# BLE113.net
KiCad netlist of a schematic drawn in Altium Designer
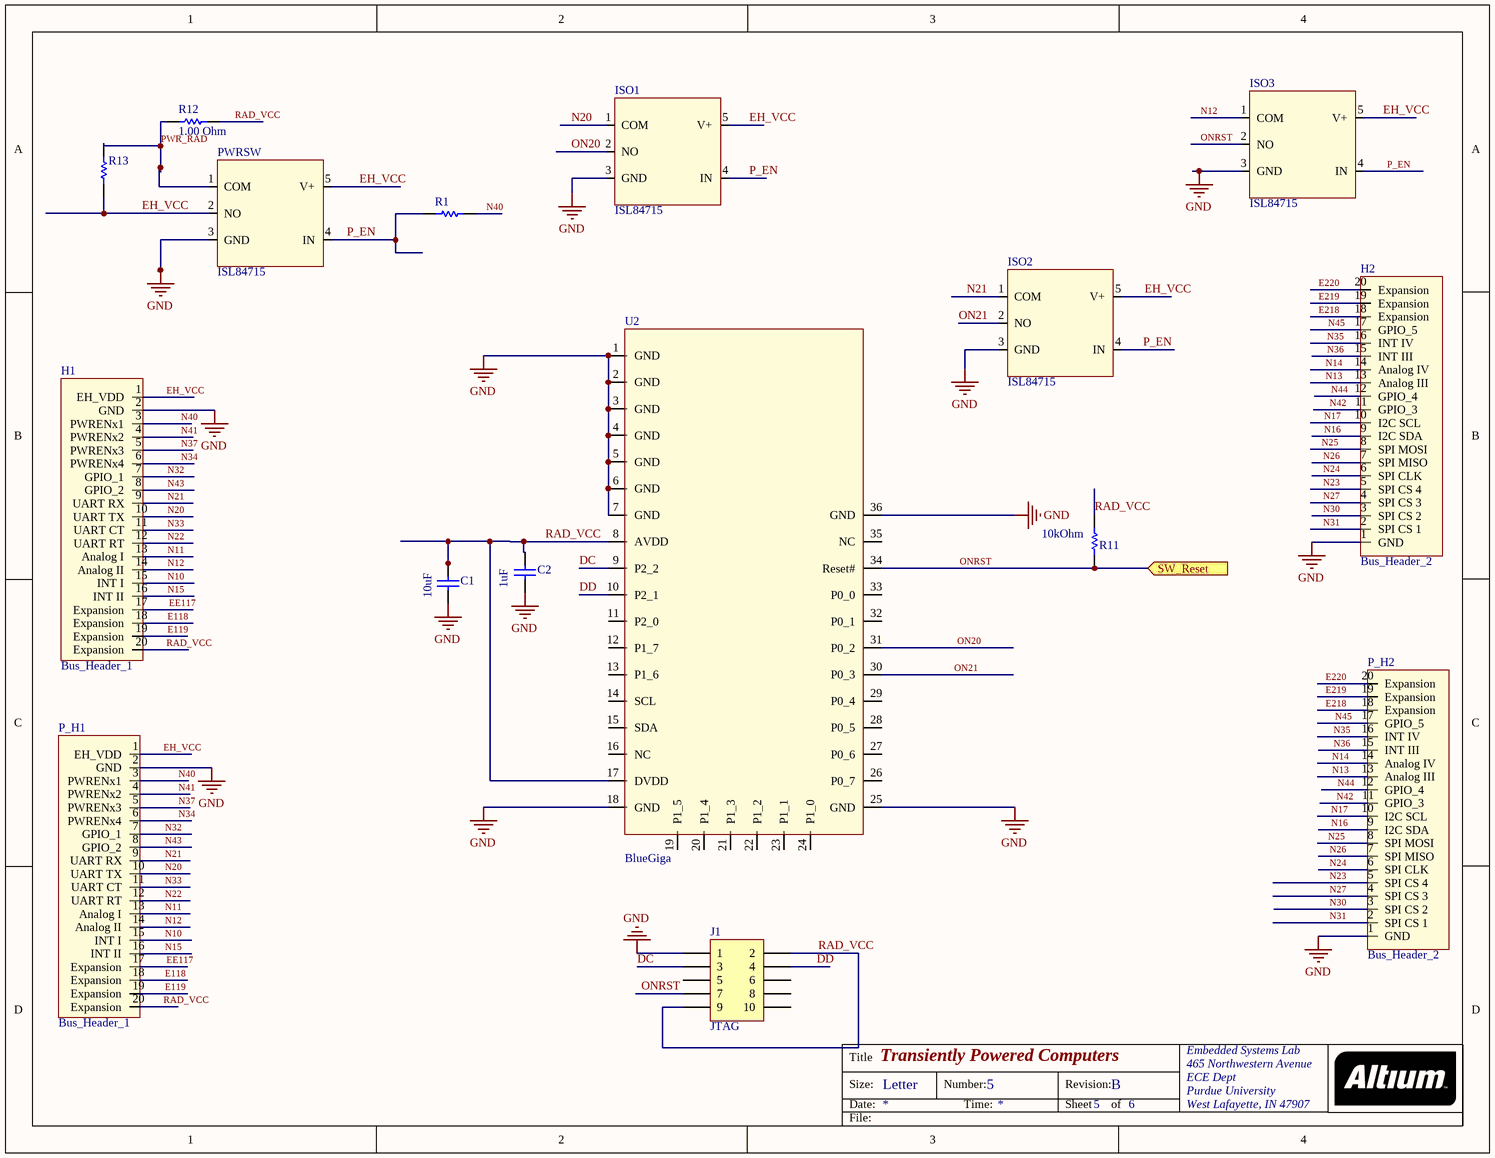
[diagram p0: BLE113.SchDoc]

(export (version "E")
  (design (tool "Eeschema 10.0.6"))
  (components
    (comp (ref "C1")
      (value "10uF")
      (footprint "CAPC0402(1005)60_N")
      (description "CAP 470nF 4V ±10% 0402 (1005 Metric) Thickness 0.6mm SMD")
      (fields (field (name "TOLERANCE") "±10%") (field (name "Comment") "CAP 470nF 4V 0402(1005)"))
      (libsource (lib "Altium Content Vault") (part "CMP-1034-02101-1"))
    )
    (comp (ref "C2")
      (value "1uF")
      (footprint "CAPC0402(1005)60_N")
      (description "CAP 470nF 4V ±10% 0402 (1005 Metric) Thickness 0.6mm SMD")
      (fields (field (name "TOLERANCE") "±10%") (field (name "Comment") "CAP 470nF 4V 0402(1005)"))
      (libsource (lib "Altium Content Vault") (part "CMP-1034-02101-1"))
    )
    (comp (ref "H1")
      (value "Bus_Header_1")
      (footprint "Male Single row 20 pin header")
      (libsource (lib "") (part "Bus_Header_1_1"))
    )
    (comp (ref "H2")
      (value "Bus_Header_2")
      (footprint "Male Single row 20 pin header")
      (libsource (lib "Basic_components_hrishi") (part "Bus_Header_2"))
    )
    (comp (ref "ISO1")
      (value "ISL84715")
      (footprint "ISL84715")
      (libsource (lib "Basic_components_hrishi") (part "ISL84715"))
    )
    (comp (ref "ISO2")
      (value "ISL84715")
      (footprint "ISL84715")
      (libsource (lib "Basic_components_hrishi") (part "ISL84715"))
    )
    (comp (ref "ISO3")
      (value "ISL84715")
      (footprint "ISL84715")
      (libsource (lib "Basic_components_hrishi") (part "ISL84715"))
    )
    (comp (ref "J1")
      (value "JTAG")
      (footprint "FTSH-105-XX-X-DV")
      (description "CC_JTAG")
      (libsource (lib "UPLINK-RX") (part "CC_JTAG"))
    )
    (comp (ref "PWRSW")
      (value "ISL84715")
      (footprint "ISL84715")
      (libsource (lib "Basic_components_hrishi") (part "ISL84715"))
    )
    (comp (ref "P_H1")
      (value "Bus_Header_1")
      (footprint "SMT 20 -pin single row female header")
      (libsource (lib "Basic_components_hrishi") (part "Bus_Header_1"))
    )
    (comp (ref "P_H2")
      (value "Bus_Header_2")
      (footprint "SMT 20 -pin single row female header")
      (libsource (lib "Basic_components_hrishi") (part "Bus_Header_2"))
    )
    (comp (ref "R1")
      (value "Jumper 0402(1005)")
      (footprint "RESC0402(1005)_N")
      (description "Jumper 0402 (1005 Metric)")
      (fields (field (name "TOLERANCE") "None"))
      (libsource (lib "Altium Content Vault") (part "CMP-1011-00001-1"))
    )
    (comp (ref "R11")
      (value "10kOhm")
      (footprint "RESC0805(2012)_M")
      (description "5R1 0.125W 5% 0805 (2012 Metric)  SMD")
      (fields (field (name "POWER") "0.125 W") (field (name "TOLERANCE") "5 %"))
      (libsource (lib "Altium Content Vault") (part "CMP-1013-00019-1"))
    )
    (comp (ref "R12")
      (value "1.00 Ohm")
      (footprint "RESC0402(1005)_N")
      (description "1R 0.063W 5% 0402 (1005 Metric)  SMD")
      (fields (field (name "POWER") "0.063 W") (field (name "TOLERANCE") "5 %"))
      (libsource (lib "Altium Content Vault") (part "CMP-1011-00002-1"))
    )
    (comp (ref "R13")
      (value "Jumper 0402(1005)")
      (footprint "RESC0402(1005)_N")
      (description "Jumper 0402 (1005 Metric)")
      (fields (field (name "TOLERANCE") "None"))
      (libsource (lib "Altium Content Vault") (part "CMP-1011-00001-1"))
    )
    (comp (ref "U2")
      (value "BlueGiga")
      (footprint "BlueGiga")
      (libsource (lib "Basic_components_hrishi") (part "BlueGiga"))
    )
  )
  (nets
    (net (code "1") (name "/DC") (class "Default")
      (node (ref "J1") (pin "3") (pinfunction "3_3") (pintype "passive"))
      (node (ref "U2") (pin "9") (pinfunction "P2_2_9") (pintype "passive"))
    )
    (net (code "2") (name "/DD") (class "Default")
      (node (ref "J1") (pin "4") (pinfunction "4_4") (pintype "passive"))
      (node (ref "U2") (pin "10") (pinfunction "P2_1_10") (pintype "passive"))
    )
    (net (code "3") (name "/E118") (class "Default")
      (node (ref "H1") (pin "18") (pinfunction "Expansion_18") (pintype "passive"))
      (node (ref "P_H1") (pin "18") (pinfunction "Expansion_18") (pintype "passive"))
    )
    (net (code "4") (name "/E119") (class "Default")
      (node (ref "H1") (pin "19") (pinfunction "Expansion_19") (pintype "passive"))
      (node (ref "P_H1") (pin "19") (pinfunction "Expansion_19") (pintype "passive"))
    )
    (net (code "5") (name "/E218") (class "Default")
      (node (ref "H2") (pin "18") (pinfunction "Expansion_18") (pintype "passive"))
      (node (ref "P_H2") (pin "18") (pinfunction "Expansion_18") (pintype "passive"))
    )
    (net (code "6") (name "/E219") (class "Default")
      (node (ref "H2") (pin "19") (pinfunction "Expansion_19") (pintype "passive"))
      (node (ref "P_H2") (pin "19") (pinfunction "Expansion_19") (pintype "passive"))
    )
    (net (code "7") (name "/E220") (class "Default")
      (node (ref "H2") (pin "20") (pinfunction "Expansion_20") (pintype "passive"))
      (node (ref "P_H2") (pin "20") (pinfunction "Expansion_20") (pintype "passive"))
    )
    (net (code "8") (name "/EE117") (class "Default")
      (node (ref "H1") (pin "17") (pinfunction "Expansion_17") (pintype "passive"))
      (node (ref "P_H1") (pin "17") (pinfunction "Expansion_17") (pintype "passive"))
    )
    (net (code "9") (name "/EH_VCC") (class "Default")
      (node (ref "H1") (pin "1") (pinfunction "EH_VDD_1") (pintype "passive"))
      (node (ref "ISO1") (pin "5") (pinfunction "V+_5") (pintype "passive"))
      (node (ref "ISO2") (pin "5") (pinfunction "V+_5") (pintype "passive"))
      (node (ref "ISO3") (pin "5") (pinfunction "V+_5") (pintype "passive"))
      (node (ref "PWRSW") (pin "2") (pinfunction "NO_2") (pintype "passive"))
      (node (ref "PWRSW") (pin "5") (pinfunction "V+_5") (pintype "passive"))
      (node (ref "P_H1") (pin "1") (pinfunction "EH_VDD_1") (pintype "passive"))
      (node (ref "R13") (pin "1") (pinfunction "1_1") (pintype "passive"))
    )
    (net (code "10") (name "/N10") (class "Default")
      (node (ref "H1") (pin "15") (pinfunction "INT_I_15") (pintype "passive"))
      (node (ref "P_H1") (pin "15") (pinfunction "INT_I_15") (pintype "passive"))
    )
    (net (code "11") (name "/N11") (class "Default")
      (node (ref "H1") (pin "13") (pinfunction "Analog_I_13") (pintype "passive"))
      (node (ref "P_H1") (pin "13") (pinfunction "Analog_I_13") (pintype "passive"))
    )
    (net (code "12") (name "/N12") (class "Default")
      (node (ref "H1") (pin "14") (pinfunction "Analog_II_14") (pintype "passive"))
      (node (ref "ISO3") (pin "1") (pinfunction "COM_1") (pintype "passive"))
      (node (ref "P_H1") (pin "14") (pinfunction "Analog_II_14") (pintype "passive"))
    )
    (net (code "13") (name "/N13") (class "Default")
      (node (ref "H2") (pin "13") (pinfunction "Analog_III_13") (pintype "passive"))
      (node (ref "P_H2") (pin "13") (pinfunction "Analog_III_13") (pintype "passive"))
    )
    (net (code "14") (name "/N14") (class "Default")
      (node (ref "H2") (pin "14") (pinfunction "Analog_IV_14") (pintype "passive"))
      (node (ref "P_H2") (pin "14") (pinfunction "Analog_IV_14") (pintype "passive"))
    )
    (net (code "15") (name "/N15") (class "Default")
      (node (ref "H1") (pin "16") (pinfunction "INT_II_16") (pintype "passive"))
      (node (ref "P_H1") (pin "16") (pinfunction "INT_II_16") (pintype "passive"))
    )
    (net (code "16") (name "/N16") (class "Default")
      (node (ref "H2") (pin "9") (pinfunction "I2C_SDA_9") (pintype "passive"))
      (node (ref "P_H2") (pin "9") (pinfunction "I2C_SDA_9") (pintype "passive"))
    )
    (net (code "17") (name "/N17") (class "Default")
      (node (ref "H2") (pin "10") (pinfunction "I2C_SCL_10") (pintype "passive"))
      (node (ref "P_H2") (pin "10") (pinfunction "I2C_SCL_10") (pintype "passive"))
    )
    (net (code "18") (name "/N20") (class "Default")
      (node (ref "H1") (pin "10") (pinfunction "UART_TX_10") (pintype "passive"))
      (node (ref "ISO1") (pin "1") (pinfunction "COM_1") (pintype "passive"))
      (node (ref "P_H1") (pin "10") (pinfunction "UART_TX_10") (pintype "passive"))
    )
    (net (code "19") (name "/N21") (class "Default")
      (node (ref "H1") (pin "9") (pinfunction "UART_RX_9") (pintype "passive"))
      (node (ref "ISO2") (pin "1") (pinfunction "COM_1") (pintype "passive"))
      (node (ref "P_H1") (pin "9") (pinfunction "UART_RX_9") (pintype "passive"))
    )
    (net (code "20") (name "/N22") (class "Default")
      (node (ref "H1") (pin "12") (pinfunction "UART_RT_12") (pintype "passive"))
      (node (ref "P_H1") (pin "12") (pinfunction "UART_RT_12") (pintype "passive"))
    )
    (net (code "21") (name "/N23") (class "Default")
      (node (ref "H2") (pin "5") (pinfunction "SPI_CS_4_5") (pintype "passive"))
      (node (ref "P_H2") (pin "5") (pinfunction "SPI_CS_4_5") (pintype "passive"))
    )
    (net (code "22") (name "/N24") (class "Default")
      (node (ref "H2") (pin "6") (pinfunction "SPI_CLK_6") (pintype "passive"))
      (node (ref "P_H2") (pin "6") (pinfunction "SPI_CLK_6") (pintype "passive"))
    )
    (net (code "23") (name "/N25") (class "Default")
      (node (ref "H2") (pin "8") (pinfunction "SPI_MOSI_8") (pintype "passive"))
      (node (ref "P_H2") (pin "8") (pinfunction "SPI_MOSI_8") (pintype "passive"))
    )
    (net (code "24") (name "/N26") (class "Default")
      (node (ref "H2") (pin "7") (pinfunction "SPI_MISO_7") (pintype "passive"))
      (node (ref "P_H2") (pin "7") (pinfunction "SPI_MISO_7") (pintype "passive"))
    )
    (net (code "25") (name "/N27") (class "Default")
      (node (ref "H2") (pin "4") (pinfunction "SPI_CS_3_4") (pintype "passive"))
      (node (ref "P_H2") (pin "4") (pinfunction "SPI_CS_3_4") (pintype "passive"))
    )
    (net (code "26") (name "/N30") (class "Default")
      (node (ref "H2") (pin "3") (pinfunction "SPI_CS_2_3") (pintype "passive"))
      (node (ref "P_H2") (pin "3") (pinfunction "SPI_CS_2_3") (pintype "passive"))
    )
    (net (code "27") (name "/N31") (class "Default")
      (node (ref "H2") (pin "2") (pinfunction "SPI_CS_1_2") (pintype "passive"))
      (node (ref "P_H2") (pin "2") (pinfunction "SPI_CS_1_2") (pintype "passive"))
    )
    (net (code "28") (name "/N32") (class "Default")
      (node (ref "H1") (pin "7") (pinfunction "GPIO_1_7") (pintype "passive"))
      (node (ref "P_H1") (pin "7") (pinfunction "GPIO_1_7") (pintype "passive"))
    )
    (net (code "29") (name "/N33") (class "Default")
      (node (ref "H1") (pin "11") (pinfunction "UART_CT_11") (pintype "passive"))
      (node (ref "P_H1") (pin "11") (pinfunction "UART_CT_11") (pintype "passive"))
    )
    (net (code "30") (name "/N34") (class "Default")
      (node (ref "H1") (pin "6") (pinfunction "PWRENx4_6") (pintype "passive"))
      (node (ref "P_H1") (pin "6") (pinfunction "PWRENx4_6") (pintype "passive"))
    )
    (net (code "31") (name "/N35") (class "Default")
      (node (ref "H2") (pin "16") (pinfunction "INT_IV_16") (pintype "passive"))
      (node (ref "P_H2") (pin "16") (pinfunction "INT_IV_16") (pintype "passive"))
    )
    (net (code "32") (name "/N36") (class "Default")
      (node (ref "H2") (pin "15") (pinfunction "INT_III_15") (pintype "passive"))
      (node (ref "P_H2") (pin "15") (pinfunction "INT_III_15") (pintype "passive"))
    )
    (net (code "33") (name "/N37") (class "Default")
      (node (ref "H1") (pin "5") (pinfunction "PWRENx3_5") (pintype "passive"))
      (node (ref "P_H1") (pin "5") (pinfunction "PWRENx3_5") (pintype "passive"))
    )
    (net (code "34") (name "/N40") (class "Default")
      (node (ref "H1") (pin "3") (pinfunction "PWRENx1_3") (pintype "passive"))
      (node (ref "P_H1") (pin "3") (pinfunction "PWRENx1_3") (pintype "passive"))
      (node (ref "R1") (pin "2") (pinfunction "2_2") (pintype "passive"))
    )
    (net (code "35") (name "/N41") (class "Default")
      (node (ref "H1") (pin "4") (pinfunction "PWRENx2_4") (pintype "passive"))
      (node (ref "P_H1") (pin "4") (pinfunction "PWRENx2_4") (pintype "passive"))
    )
    (net (code "36") (name "/N42") (class "Default")
      (node (ref "H2") (pin "11") (pinfunction "GPIO_3_11") (pintype "passive"))
      (node (ref "P_H2") (pin "11") (pinfunction "GPIO_3_11") (pintype "passive"))
    )
    (net (code "37") (name "/N43") (class "Default")
      (node (ref "H1") (pin "8") (pinfunction "GPIO_2_8") (pintype "passive"))
      (node (ref "P_H1") (pin "8") (pinfunction "GPIO_2_8") (pintype "passive"))
    )
    (net (code "38") (name "/N44") (class "Default")
      (node (ref "H2") (pin "12") (pinfunction "GPIO_4_12") (pintype "passive"))
      (node (ref "P_H2") (pin "12") (pinfunction "GPIO_4_12") (pintype "passive"))
    )
    (net (code "39") (name "/N45") (class "Default")
      (node (ref "H2") (pin "17") (pinfunction "GPIO_5_17") (pintype "passive"))
      (node (ref "P_H2") (pin "17") (pinfunction "GPIO_5_17") (pintype "passive"))
    )
    (net (code "40") (name "/ON20") (class "Default")
      (node (ref "ISO1") (pin "2") (pinfunction "NO_2") (pintype "passive"))
      (node (ref "U2") (pin "31") (pinfunction "P0_2_31") (pintype "passive"))
    )
    (net (code "41") (name "/ON21") (class "Default")
      (node (ref "ISO2") (pin "2") (pinfunction "NO_2") (pintype "passive"))
      (node (ref "U2") (pin "30") (pinfunction "P0_3_30") (pintype "passive"))
    )
    (net (code "42") (name "/ONRST") (class "Default")
      (node (ref "ISO3") (pin "2") (pinfunction "NO_2") (pintype "passive"))
      (node (ref "J1") (pin "7") (pinfunction "7_7") (pintype "passive"))
      (node (ref "R11") (pin "1") (pinfunction "1_1") (pintype "passive"))
      (node (ref "U2") (pin "34") (pinfunction "Reset#_34") (pintype "passive"))
    )
    (net (code "43") (name "/PWR_RAD") (class "Default")
      (node (ref "PWRSW") (pin "1") (pinfunction "COM_1") (pintype "passive"))
      (node (ref "R12") (pin "2") (pinfunction "2_2") (pintype "passive"))
      (node (ref "R13") (pin "2") (pinfunction "2_2") (pintype "passive"))
    )
    (net (code "44") (name "/P_EN") (class "Default")
      (node (ref "ISO1") (pin "4") (pinfunction "IN_4") (pintype "passive"))
      (node (ref "ISO2") (pin "4") (pinfunction "IN_4") (pintype "passive"))
      (node (ref "ISO3") (pin "4") (pinfunction "IN_4") (pintype "passive"))
      (node (ref "PWRSW") (pin "4") (pinfunction "IN_4") (pintype "passive"))
      (node (ref "R1") (pin "1") (pinfunction "1_1") (pintype "passive"))
    )
    (net (code "45") (name "/RAD_VCC") (class "Default")
      (node (ref "C1") (pin "2") (pinfunction "2_2") (pintype "passive"))
      (node (ref "C2") (pin "2") (pinfunction "2_2") (pintype "passive"))
      (node (ref "H1") (pin "20") (pinfunction "Expansion_20") (pintype "passive"))
      (node (ref "J1") (pin "2") (pinfunction "2_2") (pintype "passive"))
      (node (ref "J1") (pin "9") (pinfunction "9_9") (pintype "passive"))
      (node (ref "P_H1") (pin "20") (pinfunction "Expansion_20") (pintype "passive"))
      (node (ref "R11") (pin "2") (pinfunction "2_2") (pintype "passive"))
      (node (ref "R12") (pin "1") (pinfunction "1_1") (pintype "passive"))
      (node (ref "U2") (pin "17") (pinfunction "DVDD_17") (pintype "power_in"))
      (node (ref "U2") (pin "8") (pinfunction "AVDD_8") (pintype "power_in"))
    )
    (net (code "46") (name "GND") (class "Default")
      (node (ref "C1") (pin "1") (pinfunction "1_1") (pintype "passive"))
      (node (ref "C2") (pin "1") (pinfunction "1_1") (pintype "passive"))
      (node (ref "H1") (pin "2") (pinfunction "GND_2") (pintype "passive"))
      (node (ref "H2") (pin "1") (pinfunction "GND_1") (pintype "passive"))
      (node (ref "ISO1") (pin "3") (pinfunction "GND_3") (pintype "passive"))
      (node (ref "ISO2") (pin "3") (pinfunction "GND_3") (pintype "passive"))
      (node (ref "ISO3") (pin "3") (pinfunction "GND_3") (pintype "passive"))
      (node (ref "J1") (pin "1") (pinfunction "1_1") (pintype "passive"))
      (node (ref "PWRSW") (pin "3") (pinfunction "GND_3") (pintype "passive"))
      (node (ref "P_H1") (pin "2") (pinfunction "GND_2") (pintype "passive"))
      (node (ref "P_H2") (pin "1") (pinfunction "GND_1") (pintype "passive"))
      (node (ref "U2") (pin "1") (pinfunction "GND_1") (pintype "passive"))
      (node (ref "U2") (pin "18") (pinfunction "GND_18") (pintype "passive"))
      (node (ref "U2") (pin "2") (pinfunction "GND_2") (pintype "passive"))
      (node (ref "U2") (pin "25") (pinfunction "GND_25") (pintype "passive"))
      (node (ref "U2") (pin "3") (pinfunction "GND_3") (pintype "passive"))
      (node (ref "U2") (pin "36") (pinfunction "GND_36") (pintype "passive"))
      (node (ref "U2") (pin "4") (pinfunction "GND_4") (pintype "passive"))
      (node (ref "U2") (pin "5") (pinfunction "GND_5") (pintype "passive"))
      (node (ref "U2") (pin "6") (pinfunction "GND_6") (pintype "passive"))
      (node (ref "U2") (pin "7") (pinfunction "GND_7") (pintype "passive"))
    )
    (net (code "47") (name "unconnected-(J1-Pad5)") (class "Default")
      (node (ref "J1") (pin "5") (pinfunction "5_5") (pintype "passive"))
    )
    (net (code "48") (name "unconnected-(J1-Pad6)") (class "Default")
      (node (ref "J1") (pin "6") (pinfunction "6_6") (pintype "passive"))
    )
    (net (code "49") (name "unconnected-(J1-Pad8)") (class "Default")
      (node (ref "J1") (pin "8") (pinfunction "8_8") (pintype "passive"))
    )
    (net (code "50") (name "unconnected-(J1-Pad10)") (class "Default")
      (node (ref "J1") (pin "10") (pinfunction "10_10") (pintype "passive"))
    )
    (net (code "51") (name "unconnected-(U2-NC-Pad16)") (class "Default")
      (node (ref "U2") (pin "16") (pinfunction "NC_16") (pintype "passive"))
    )
    (net (code "52") (name "unconnected-(U2-NC-Pad35)") (class "Default")
      (node (ref "U2") (pin "35") (pinfunction "NC_35") (pintype "passive"))
    )
    (net (code "53") (name "unconnected-(U2-P0_0-Pad33)") (class "Default")
      (node (ref "U2") (pin "33") (pinfunction "P0_0_33") (pintype "passive"))
    )
    (net (code "54") (name "unconnected-(U2-P0_1-Pad32)") (class "Default")
      (node (ref "U2") (pin "32") (pinfunction "P0_1_32") (pintype "passive"))
    )
    (net (code "55") (name "unconnected-(U2-P0_4-Pad29)") (class "Default")
      (node (ref "U2") (pin "29") (pinfunction "P0_4_29") (pintype "passive"))
    )
    (net (code "56") (name "unconnected-(U2-P0_5-Pad28)") (class "Default")
      (node (ref "U2") (pin "28") (pinfunction "P0_5_28") (pintype "passive"))
    )
    (net (code "57") (name "unconnected-(U2-P0_6-Pad27)") (class "Default")
      (node (ref "U2") (pin "27") (pinfunction "P0_6_27") (pintype "passive"))
    )
    (net (code "58") (name "unconnected-(U2-P0_7-Pad26)") (class "Default")
      (node (ref "U2") (pin "26") (pinfunction "P0_7_26") (pintype "passive"))
    )
    (net (code "59") (name "unconnected-(U2-P1_0-Pad24)") (class "Default")
      (node (ref "U2") (pin "24") (pinfunction "P1_0_24") (pintype "passive"))
    )
    (net (code "60") (name "unconnected-(U2-P1_1-Pad23)") (class "Default")
      (node (ref "U2") (pin "23") (pinfunction "P1_1_23") (pintype "passive"))
    )
    (net (code "61") (name "unconnected-(U2-P1_2-Pad22)") (class "Default")
      (node (ref "U2") (pin "22") (pinfunction "P1_2_22") (pintype "passive"))
    )
    (net (code "62") (name "unconnected-(U2-P1_3-Pad21)") (class "Default")
      (node (ref "U2") (pin "21") (pinfunction "P1_3_21") (pintype "passive"))
    )
    (net (code "63") (name "unconnected-(U2-P1_4-Pad20)") (class "Default")
      (node (ref "U2") (pin "20") (pinfunction "P1_4_20") (pintype "passive"))
    )
    (net (code "64") (name "unconnected-(U2-P1_5-Pad19)") (class "Default")
      (node (ref "U2") (pin "19") (pinfunction "P1_5_19") (pintype "passive"))
    )
    (net (code "65") (name "unconnected-(U2-P1_6-Pad13)") (class "Default")
      (node (ref "U2") (pin "13") (pinfunction "P1_6_13") (pintype "passive"))
    )
    (net (code "66") (name "unconnected-(U2-P1_7-Pad12)") (class "Default")
      (node (ref "U2") (pin "12") (pinfunction "P1_7_12") (pintype "passive"))
    )
    (net (code "67") (name "unconnected-(U2-P2_0-Pad11)") (class "Default")
      (node (ref "U2") (pin "11") (pinfunction "P2_0_11") (pintype "passive"))
    )
    (net (code "68") (name "unconnected-(U2-SCL-Pad14)") (class "Default")
      (node (ref "U2") (pin "14") (pinfunction "SCL_14") (pintype "passive"))
    )
    (net (code "69") (name "unconnected-(U2-SDA-Pad15)") (class "Default")
      (node (ref "U2") (pin "15") (pinfunction "SDA_15") (pintype "passive"))
    )
  )
)
